# PV_MCONTROL_IO.net
KiCad netlist of a schematic drawn in Altium Designer
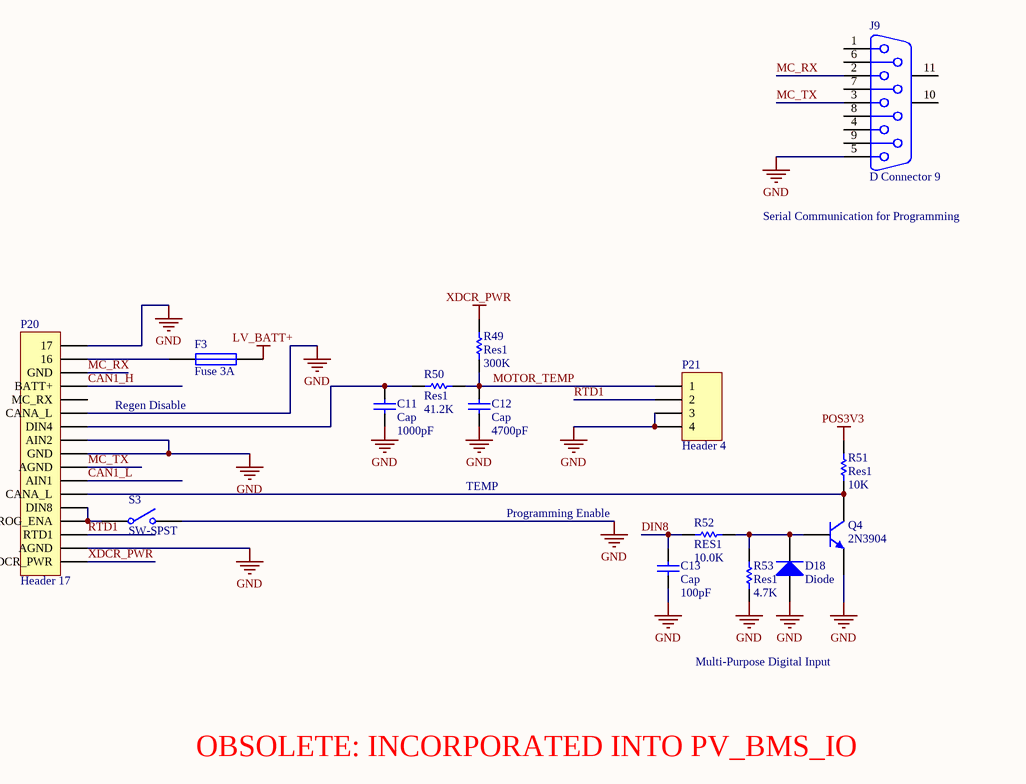
[diagram p0: PV_MCONTROL_IO.SchDoc]

(export (version "E")
  (design (tool "Eeschema 10.0.6"))
  (components
    (comp (ref "C11")
      (value "Cap")
      (footprint "RAD-0.3")
      (description "Capacitor")
      (fields (field (name "ALTIUM_VALUE") "1000pF") (field (name "PUBLISHER") "Altium Limited"))
      (libsource (lib "Miscellaneous Devices") (part "Cap"))
    )
    (comp (ref "C12")
      (value "Cap")
      (footprint "RAD-0.3")
      (description "Capacitor")
      (fields (field (name "ALTIUM_VALUE") "4700pF") (field (name "PUBLISHER") "Altium Limited"))
      (libsource (lib "Miscellaneous Devices") (part "Cap"))
    )
    (comp (ref "C13")
      (value "Cap")
      (footprint "RAD-0.3")
      (description "Capacitor")
      (fields (field (name "ALTIUM_VALUE") "100pF") (field (name "PUBLISHER") "Altium Limited"))
      (libsource (lib "Miscellaneous Devices") (part "Cap"))
    )
    (comp (ref "D18")
      (value "Diode")
      (footprint "SMC")
      (description "Default Diode")
      (fields (field (name "PUBLISHER") "Altium Limited"))
      (libsource (lib "Miscellaneous Devices") (part "Diode"))
    )
    (comp (ref "F3")
      (value "Fuse 3A")
      (footprint "1A FUSE HOLDER")
      (description "Fuse")
      (fields (field (name "PUBLISHER") "Altium Limited"))
      (libsource (lib "Miscellaneous Devices") (part "Fuse 1"))
    )
    (comp (ref "J9")
      (value "D Connector 9")
      (footprint "DSUB1.385-2H9")
      (description "Receptacle Assembly, 9 Position, Right Angle")
      (fields (field (name "PUBLISHER") "Altium Limited"))
      (libsource (lib "Miscellaneous Connectors") (part "D Connector 9"))
    )
    (comp (ref "P20")
      (value "Header 17")
      (footprint "HDR1X17")
      (description "Header, 17-Pin")
      (fields (field (name "PUBLISHER") "Altium Limited"))
      (libsource (lib "Miscellaneous Connectors") (part "Header 17"))
    )
    (comp (ref "P21")
      (value "Header 4")
      (footprint "HDR1X4")
      (description "Header, 4-Pin")
      (fields (field (name "PUBLISHER") "Altium Limited"))
      (libsource (lib "Miscellaneous Connectors") (part "Header 4"))
    )
    (comp (ref "Q4")
      (value "2N3904")
      (footprint "TO-92A")
      (description "NPN General Purpose Amplifier")
      (fields (field (name "PUBLISHER") "Altium Limited"))
      (libsource (lib "Miscellaneous Devices") (part "2N3904"))
    )
    (comp (ref "R49")
      (value "Res1")
      (footprint "AXIAL-0.3")
      (description "Resistor")
      (fields (field (name "ALTIUM_VALUE") "300K") (field (name "PUBLISHER") "Altium Limited"))
      (libsource (lib "Miscellaneous Devices") (part "Res1"))
    )
    (comp (ref "R50")
      (value "Res1")
      (footprint "AXIAL-0.3")
      (description "Resistor")
      (fields (field (name "ALTIUM_VALUE") "41.2K") (field (name "PUBLISHER") "Altium Limited"))
      (libsource (lib "Miscellaneous Devices") (part "Res1"))
    )
    (comp (ref "R51")
      (value "Res1")
      (footprint "AXIAL-0.3")
      (description "Resistor")
      (fields (field (name "ALTIUM_VALUE") "10K") (field (name "PUBLISHER") "Altium Limited"))
      (libsource (lib "Miscellaneous Devices") (part "Res1"))
    )
    (comp (ref "R52")
      (value "RES1")
      (footprint "AXIAL-0.3")
      (description "Resistor")
      (fields (field (name "ALTIUM_VALUE") "10.0K") (field (name "PUBLISHER") "Altium Limited"))
      (libsource (lib "Miscellaneous Devices") (part "Res1"))
    )
    (comp (ref "R53")
      (value "Res1")
      (footprint "AXIAL-0.3")
      (description "Resistor")
      (fields (field (name "ALTIUM_VALUE") "4.7K") (field (name "PUBLISHER") "Altium Limited"))
      (libsource (lib "Miscellaneous Devices") (part "Res1"))
    )
    (comp (ref "S3")
      (value "SW-SPST")
      (footprint "SPST-2")
      (description "Single-Pole, Single-Throw Switch")
      (fields (field (name "PUBLISHER") "Altium Limited"))
      (libsource (lib "Miscellaneous Devices") (part "SW-SPST"))
    )
  )
  (nets
    (net (code "1") (name "/CAN1_H") (class "Default")
      (node (ref "P20") (pin "14") (pinfunction "BATT+_14") (pintype "passive"))
    )
    (net (code "2") (name "/CAN1_L") (class "Default")
      (node (ref "P20") (pin "7") (pinfunction "AIN1_7") (pintype "passive"))
    )
    (net (code "3") (name "/DIN8") (class "Default")
      (node (ref "C13") (pin "2") (pinfunction "2_2") (pintype "passive"))
      (node (ref "R52") (pin "1") (pinfunction "1_1") (pintype "passive"))
    )
    (net (code "4") (name "/MC_RX") (class "Default")
      (node (ref "J9") (pin "2") (pinfunction "2_2") (pintype "passive"))
      (node (ref "P20") (pin "15") (pinfunction "GND_15") (pintype "passive"))
    )
    (net (code "5") (name "/MC_TX") (class "Default")
      (node (ref "J9") (pin "3") (pinfunction "3_3") (pintype "passive"))
      (node (ref "P20") (pin "8") (pinfunction "AGND_8") (pintype "passive"))
    )
    (net (code "6") (name "/MOTOR_TEMP") (class "Default")
      (node (ref "C12") (pin "2") (pinfunction "2_2") (pintype "passive"))
      (node (ref "P21") (pin "1") (pinfunction "1_1") (pintype "passive"))
      (node (ref "R49") (pin "1") (pinfunction "1_1") (pintype "passive"))
      (node (ref "R50") (pin "1") (pinfunction "1_1") (pintype "passive"))
    )
    (net (code "7") (name "/RTD1") (class "Default")
      (node (ref "P20") (pin "3") (pinfunction "RTD1_3") (pintype "passive"))
      (node (ref "P21") (pin "2") (pinfunction "2_2") (pintype "passive"))
    )
    (net (code "8") (name "GND") (class "Default")
      (node (ref "C11") (pin "1") (pinfunction "1_1") (pintype "passive"))
      (node (ref "C12") (pin "1") (pinfunction "1_1") (pintype "passive"))
      (node (ref "C13") (pin "1") (pinfunction "1_1") (pintype "passive"))
      (node (ref "D18") (pin "1") (pinfunction "A_1") (pintype "passive"))
      (node (ref "J9") (pin "5") (pinfunction "5_5") (pintype "passive"))
      (node (ref "P20") (pin "10") (pinfunction "AIN2_10") (pintype "passive"))
      (node (ref "P20") (pin "12") (pinfunction "CANA_L_12") (pintype "passive"))
      (node (ref "P20") (pin "17") (pinfunction "17_17") (pintype "passive"))
      (node (ref "P20") (pin "2") (pinfunction "AGND_2") (pintype "passive"))
      (node (ref "P20") (pin "9") (pinfunction "GND_9") (pintype "passive"))
      (node (ref "P21") (pin "3") (pinfunction "3_3") (pintype "passive"))
      (node (ref "P21") (pin "4") (pinfunction "4_4") (pintype "passive"))
      (node (ref "Q4") (pin "1") (pinfunction "E_1") (pintype "passive"))
      (node (ref "R53") (pin "1") (pinfunction "1_1") (pintype "passive"))
      (node (ref "S3") (pin "2") (pinfunction "NO_2") (pintype "passive"))
    )
    (net (code "9") (name "LV_BATT+") (class "Default")
      (node (ref "F3") (pin "2") (pinfunction "2_2") (pintype "passive"))
    )
    (net (code "10") (name "Net-(D18-K)") (class "Default")
      (node (ref "D18") (pin "2") (pinfunction "K_2") (pintype "passive"))
      (node (ref "Q4") (pin "2") (pinfunction "B_2") (pintype "passive"))
      (node (ref "R52") (pin "2") (pinfunction "2_2") (pintype "passive"))
      (node (ref "R53") (pin "2") (pinfunction "2_2") (pintype "passive"))
    )
    (net (code "11") (name "Net-(F3-Pad1)") (class "Default")
      (node (ref "F3") (pin "1") (pinfunction "1_1") (pintype "passive"))
      (node (ref "P20") (pin "16") (pinfunction "16_16") (pintype "passive"))
    )
    (net (code "12") (name "Net-(P20-DIN4)") (class "Default")
      (node (ref "C11") (pin "2") (pinfunction "2_2") (pintype "passive"))
      (node (ref "P20") (pin "11") (pinfunction "DIN4_11") (pintype "passive"))
      (node (ref "R50") (pin "2") (pinfunction "2_2") (pintype "passive"))
    )
    (net (code "13") (name "Net-(P20-DIN8)") (class "Default")
      (node (ref "P20") (pin "4") (pinfunction "/PROG_ENA_4") (pintype "passive"))
      (node (ref "P20") (pin "5") (pinfunction "DIN8_5") (pintype "passive"))
      (node (ref "S3") (pin "1") (pinfunction "COMMON_1") (pintype "passive"))
    )
    (net (code "14") (name "Net-(Q4-C)") (class "Default")
      (node (ref "P20") (pin "6") (pinfunction "CANA_L_6") (pintype "passive"))
      (node (ref "Q4") (pin "3") (pinfunction "C_3") (pintype "passive"))
      (node (ref "R51") (pin "1") (pinfunction "1_1") (pintype "passive"))
    )
    (net (code "15") (name "POS3V3") (class "Default")
      (node (ref "R51") (pin "2") (pinfunction "2_2") (pintype "passive"))
    )
    (net (code "16") (name "XDCR_PWR") (class "Default")
      (node (ref "P20") (pin "1") (pinfunction "XDCR_PWR_1") (pintype "passive"))
      (node (ref "R49") (pin "2") (pinfunction "2_2") (pintype "passive"))
    )
    (net (code "17") (name "unconnected-(J9-MH1-Pad10)") (class "Default")
      (node (ref "J9") (pin "10") (pinfunction "MH1_10") (pintype "passive"))
    )
    (net (code "18") (name "unconnected-(J9-MH2-Pad11)") (class "Default")
      (node (ref "J9") (pin "11") (pinfunction "MH2_11") (pintype "passive"))
    )
    (net (code "19") (name "unconnected-(J9-Pad1)") (class "Default")
      (node (ref "J9") (pin "1") (pinfunction "1_1") (pintype "passive"))
    )
    (net (code "20") (name "unconnected-(J9-Pad4)") (class "Default")
      (node (ref "J9") (pin "4") (pinfunction "4_4") (pintype "passive"))
    )
    (net (code "21") (name "unconnected-(J9-Pad6)") (class "Default")
      (node (ref "J9") (pin "6") (pinfunction "6_6") (pintype "passive"))
    )
    (net (code "22") (name "unconnected-(J9-Pad7)") (class "Default")
      (node (ref "J9") (pin "7") (pinfunction "7_7") (pintype "passive"))
    )
    (net (code "23") (name "unconnected-(J9-Pad8)") (class "Default")
      (node (ref "J9") (pin "8") (pinfunction "8_8") (pintype "passive"))
    )
    (net (code "24") (name "unconnected-(J9-Pad9)") (class "Default")
      (node (ref "J9") (pin "9") (pinfunction "9_9") (pintype "passive"))
    )
    (net (code "25") (name "unconnected-(P20-MC_RX-Pad13)") (class "Default")
      (node (ref "P20") (pin "13") (pinfunction "MC_RX_13") (pintype "passive"))
    )
  )
)
